# IntegratedSensor.net
KiCad netlist of a schematic drawn in EAGLE
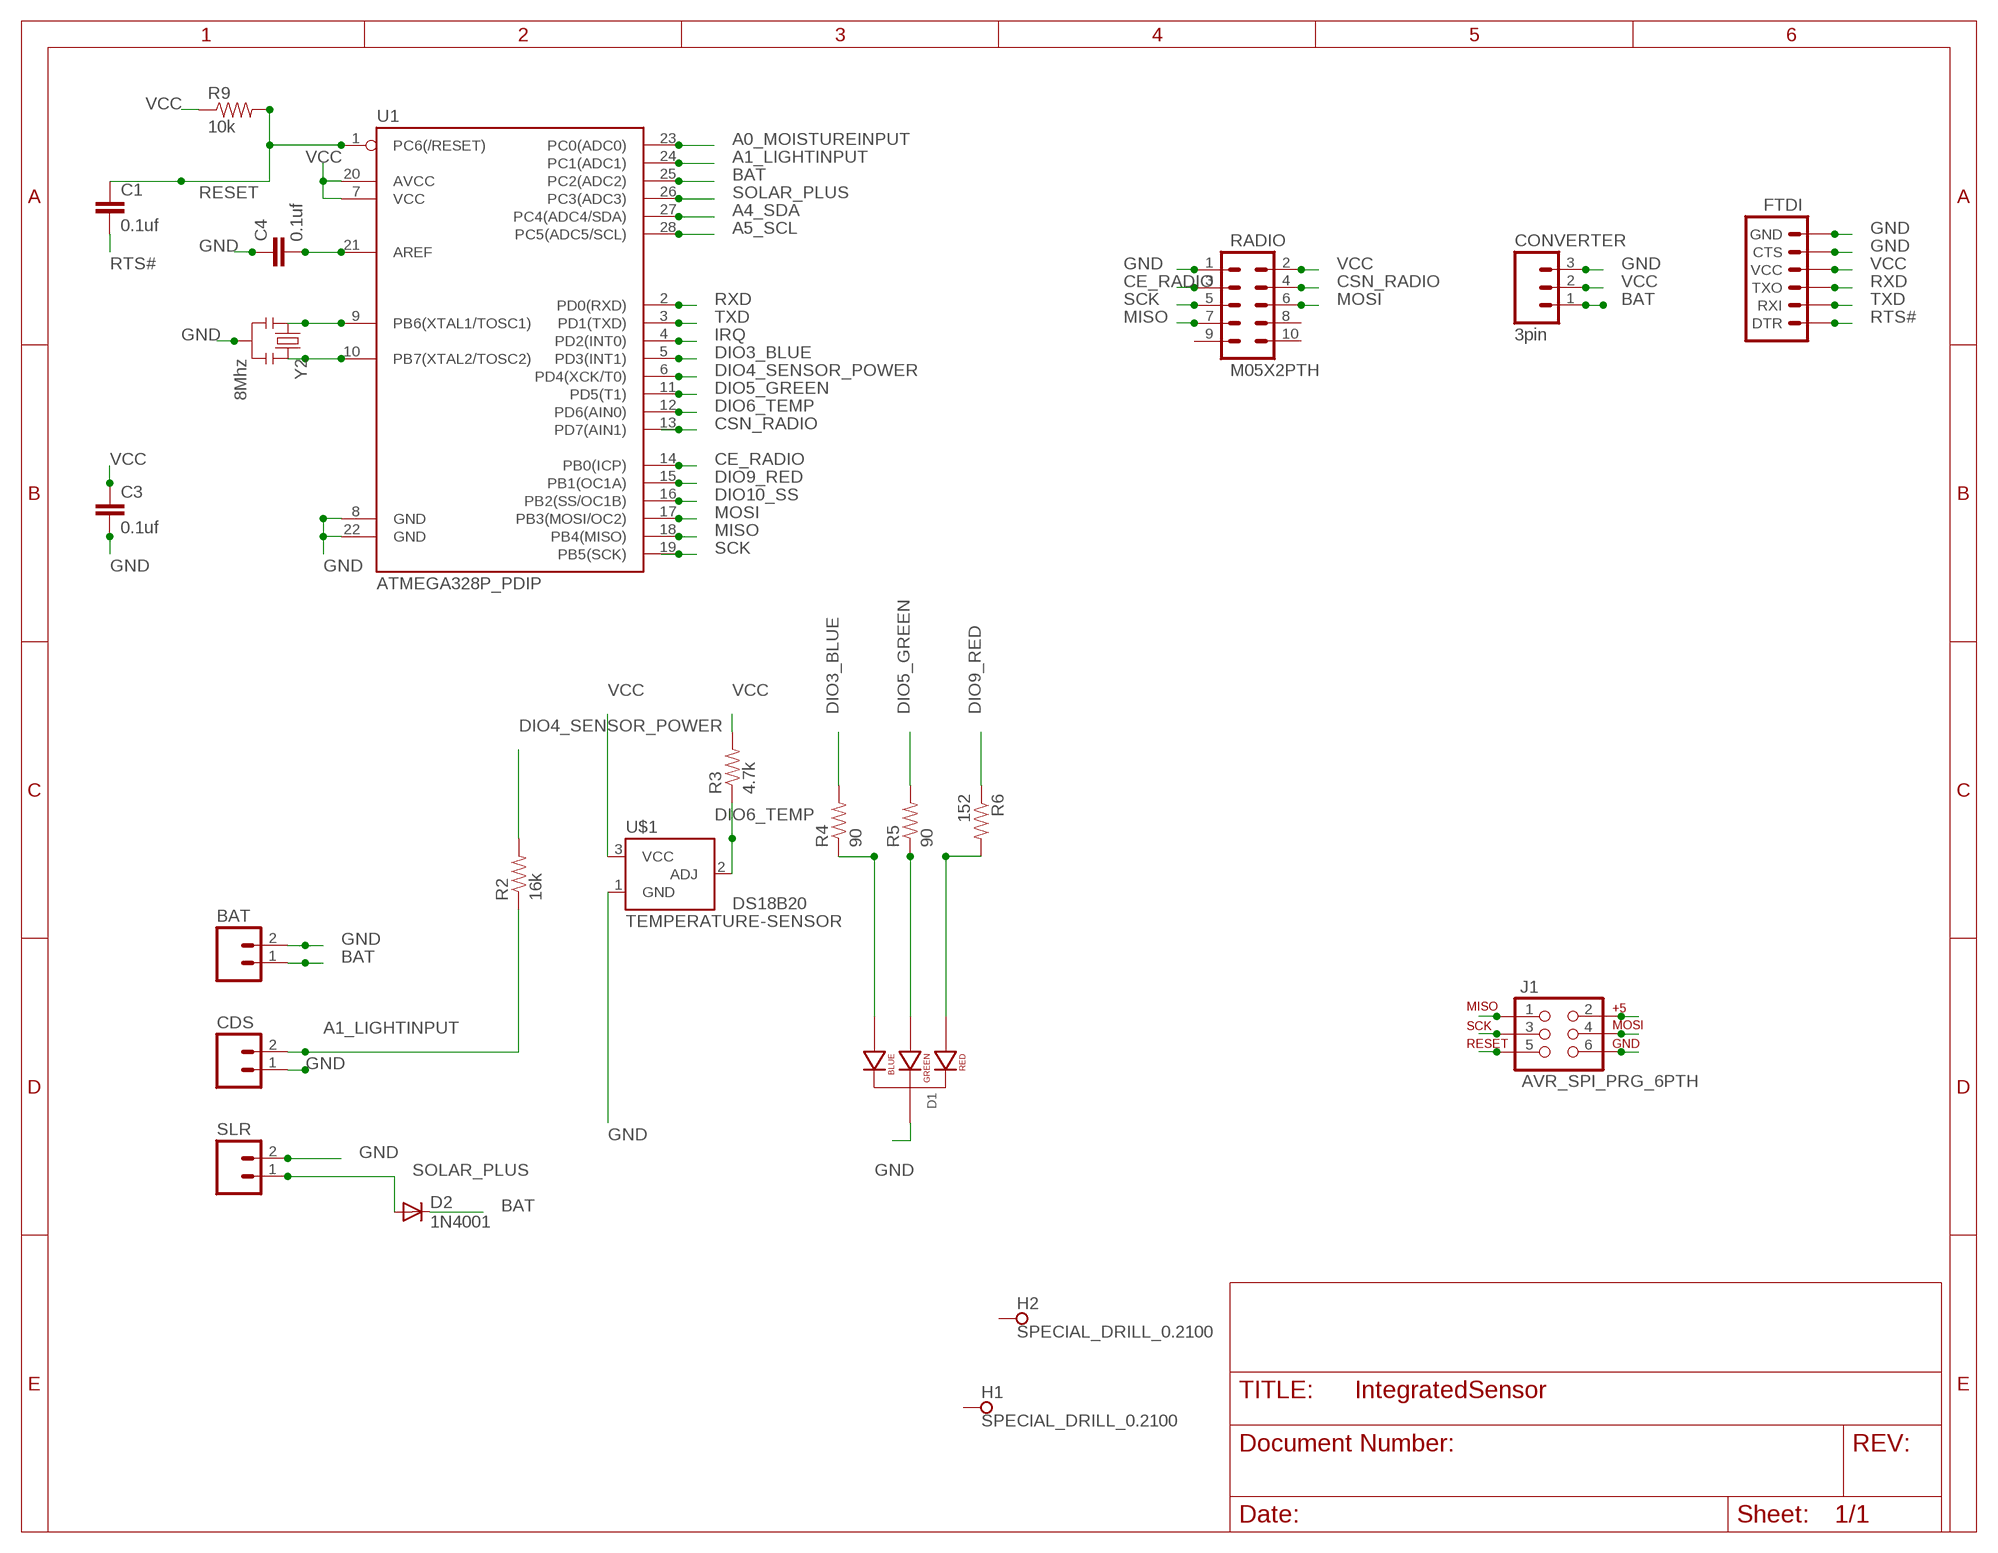
[diagram p0: schematic, sheet 1]

(export (version "E")
  (design (tool "Eeschema 10.0.6"))
  (components
    (comp (ref "BAT")
      (value "M02PTH")
      (footprint "eagle-import:1X02")
      (libsource (lib "eagle-import") (part "M02PTH"))
    )
    (comp (ref "C1")
      (value "0.1uf")
      (footprint "eagle-import:CAP-PTH-SMALL")
      (libsource (lib "eagle-import") (part "CAPPTH"))
    )
    (comp (ref "C3")
      (value "0.1uf")
      (footprint "eagle-import:CAP-PTH-SMALL")
      (libsource (lib "eagle-import") (part "CAPPTH"))
    )
    (comp (ref "C4")
      (value "0.1uf")
      (footprint "eagle-import:CAP-PTH-SMALL")
      (libsource (lib "eagle-import") (part "CAPPTH"))
    )
    (comp (ref "CDS")
      (value "M02PTH")
      (footprint "eagle-import:1X02")
      (libsource (lib "eagle-import") (part "M02PTH"))
    )
    (comp (ref "CONVERTER")
      (value "3pin")
      (footprint "eagle-import:1X03")
      (libsource (lib "eagle-import") (part "M03PTH"))
    )
    (comp (ref "D1")
      (value "LED-RGB-CC-THRUCLEAR")
      (footprint "eagle-import:LED-RGB-THRU")
      (libsource (lib "eagle-import") (part "LED-RGB-CC-THRUCLEAR"))
    )
    (comp (ref "D2")
      (value "1N4001")
      (footprint "eagle-import:DIODE-1N4001")
      (libsource (lib "eagle-import") (part "DIODEPTH"))
    )
    (comp (ref "FTDI")
      (value "ARDUINO_SERIAL_PROGRAMPTH")
      (footprint "eagle-import:1X06")
      (libsource (lib "eagle-import") (part "ARDUINO_SERIAL_PROGRAMPTH"))
    )
    (comp (ref "H1")
      (value "SPECIAL_DRILL_0.2100")
      (footprint "eagle-import:PAD_0.2100")
      (libsource (lib "eagle-import") (part "SPECIAL_DRILL_0.2100"))
    )
    (comp (ref "H2")
      (value "SPECIAL_DRILL_0.2100")
      (footprint "eagle-import:PAD_0.2100")
      (libsource (lib "eagle-import") (part "SPECIAL_DRILL_0.2100"))
    )
    (comp (ref "J1")
      (value "AVR_SPI_PRG_6PTH")
      (footprint "eagle-import:2X3")
      (libsource (lib "eagle-import") (part "AVR_SPI_PRG_6PTH"))
    )
    (comp (ref "R2")
      (value "16k")
      (footprint "eagle-import:1_6W-RES")
      (libsource (lib "eagle-import") (part "RESISTORPTH-1/6W"))
    )
    (comp (ref "R3")
      (value "4.7k")
      (footprint "eagle-import:1_6W-RES")
      (libsource (lib "eagle-import") (part "RESISTORPTH-1/6W"))
    )
    (comp (ref "R4")
      (value "90")
      (footprint "eagle-import:1_6W-RES")
      (libsource (lib "eagle-import") (part "RESISTORPTH-1/6W"))
    )
    (comp (ref "R5")
      (value "90")
      (footprint "eagle-import:1_6W-RES")
      (libsource (lib "eagle-import") (part "RESISTORPTH-1/6W"))
    )
    (comp (ref "R6")
      (value "152")
      (footprint "eagle-import:1_6W-RES")
      (libsource (lib "eagle-import") (part "RESISTORPTH-1/6W"))
    )
    (comp (ref "R9")
      (value "10k")
      (footprint "eagle-import:1_6W-RES")
      (libsource (lib "eagle-import") (part "RESISTORPTH-1/6W"))
    )
    (comp (ref "RADIO")
      (value "M05X2PTH")
      (footprint "eagle-import:AVR_ICSP")
      (libsource (lib "eagle-import") (part "M05X2PTH"))
    )
    (comp (ref "SLR")
      (value "M02PTH")
      (footprint "eagle-import:1X02")
      (libsource (lib "eagle-import") (part "M02PTH"))
    )
    (comp (ref "U$1")
      (value "TEMPERATURE-SENSOR")
      (footprint "eagle-import:TO-92")
      (fields (field (name "PARTNAME") "DS18B20"))
      (libsource (lib "eagle-import") (part "TEMPERATURE-SENSOR"))
    )
    (comp (ref "U1")
      (value "ATMEGA328P_PDIP")
      (footprint "eagle-import:DIL28-3")
      (libsource (lib "eagle-import") (part "ATMEGA328P_PDIP"))
    )
    (comp (ref "Y2")
      (value "8Mhz")
      (footprint "eagle-import:RESONATOR-PTH")
      (libsource (lib "eagle-import") (part "RESONATORPTH"))
    )
  )
  (nets
    (net (code "1") (name "/A0_MOISTUREINPUT") (class "Default")
      (node (ref "U1") (pin "23") (pinfunction "PC0(ADC0)_23") (pintype "bidirectional"))
    )
    (net (code "2") (name "/A1_LIGHTINPUT") (class "Default")
      (node (ref "CDS") (pin "2") (pinfunction "2_2") (pintype "passive"))
      (node (ref "R2") (pin "1") (pinfunction "1_1") (pintype "passive"))
      (node (ref "U1") (pin "24") (pinfunction "PC1(ADC1)_24") (pintype "bidirectional"))
    )
    (net (code "3") (name "/A4_SDA") (class "Default")
      (node (ref "U1") (pin "27") (pinfunction "PC4(ADC4/SDA)_27") (pintype "bidirectional"))
    )
    (net (code "4") (name "/A5_SCL") (class "Default")
      (node (ref "U1") (pin "28") (pinfunction "PC5(ADC5/SCL)_28") (pintype "bidirectional"))
    )
    (net (code "5") (name "/BAT") (class "Default")
      (node (ref "BAT") (pin "1") (pinfunction "1_1") (pintype "passive"))
      (node (ref "CONVERTER") (pin "1") (pinfunction "1_1") (pintype "passive"))
      (node (ref "D2") (pin "C") (pinfunction "C_C") (pintype "passive"))
      (node (ref "U1") (pin "25") (pinfunction "PC2(ADC2)_25") (pintype "bidirectional"))
    )
    (net (code "6") (name "/CE_RADIO") (class "Default")
      (node (ref "RADIO") (pin "3") (pinfunction "3_3") (pintype "passive"))
      (node (ref "U1") (pin "14") (pinfunction "PB0(ICP)_14") (pintype "bidirectional"))
    )
    (net (code "7") (name "/CSN_RADIO") (class "Default")
      (node (ref "RADIO") (pin "4") (pinfunction "4_4") (pintype "passive"))
      (node (ref "U1") (pin "13") (pinfunction "PD7(AIN1)_13") (pintype "bidirectional"))
    )
    (net (code "8") (name "/DIO3_BLUE") (class "Default")
      (node (ref "R4") (pin "2") (pinfunction "2_2") (pintype "passive"))
      (node (ref "U1") (pin "5") (pinfunction "PD3(INT1)_5") (pintype "bidirectional"))
    )
    (net (code "9") (name "/DIO4_SENSOR_POWER") (class "Default")
      (node (ref "R2") (pin "2") (pinfunction "2_2") (pintype "passive"))
      (node (ref "U1") (pin "6") (pinfunction "PD4(XCK/T0)_6") (pintype "bidirectional"))
    )
    (net (code "10") (name "/DIO5_GREEN") (class "Default")
      (node (ref "R5") (pin "2") (pinfunction "2_2") (pintype "passive"))
      (node (ref "U1") (pin "11") (pinfunction "PD5(T1)_11") (pintype "bidirectional"))
    )
    (net (code "11") (name "/DIO6_TEMP") (class "Default")
      (node (ref "R3") (pin "1") (pinfunction "1_1") (pintype "passive"))
      (node (ref "U$1") (pin "2") (pinfunction "ADJ_2") (pintype "bidirectional"))
      (node (ref "U1") (pin "12") (pinfunction "PD6(AIN0)_12") (pintype "bidirectional"))
    )
    (net (code "12") (name "/DIO9_RED") (class "Default")
      (node (ref "R6") (pin "1") (pinfunction "1_1") (pintype "passive"))
      (node (ref "U1") (pin "15") (pinfunction "PB1(OC1A)_15") (pintype "bidirectional"))
    )
    (net (code "13") (name "/DIO10_SS") (class "Default")
      (node (ref "U1") (pin "16") (pinfunction "PB2(SS/OC1B)_16") (pintype "bidirectional"))
    )
    (net (code "14") (name "/GND") (class "Default")
      (node (ref "BAT") (pin "2") (pinfunction "2_2") (pintype "passive"))
      (node (ref "C3") (pin "2") (pinfunction "2_2") (pintype "passive"))
      (node (ref "C4") (pin "1") (pinfunction "1_1") (pintype "passive"))
      (node (ref "CDS") (pin "1") (pinfunction "1_1") (pintype "passive"))
      (node (ref "CONVERTER") (pin "3") (pinfunction "3_3") (pintype "passive"))
      (node (ref "D1") (pin "2") (pinfunction "CATHODE_2") (pintype "bidirectional"))
      (node (ref "FTDI") (pin "5") (pinfunction "CTS_5") (pintype "passive"))
      (node (ref "FTDI") (pin "6") (pinfunction "GND_6") (pintype "passive"))
      (node (ref "J1") (pin "6") (pinfunction "6_6") (pintype "passive"))
      (node (ref "RADIO") (pin "1") (pinfunction "1_1") (pintype "passive"))
      (node (ref "SLR") (pin "2") (pinfunction "2_2") (pintype "passive"))
      (node (ref "U$1") (pin "1") (pinfunction "GND_1") (pintype "bidirectional"))
      (node (ref "U1") (pin "22") (pinfunction "GND_22") (pintype "bidirectional"))
      (node (ref "U1") (pin "8") (pinfunction "GND_8") (pintype "bidirectional"))
      (node (ref "Y2") (pin "2") (pinfunction "2_2") (pintype "passive"))
    )
    (net (code "15") (name "/IRQ") (class "Default")
      (node (ref "U1") (pin "4") (pinfunction "PD2(INT0)_4") (pintype "bidirectional"))
    )
    (net (code "16") (name "/MISO") (class "Default")
      (node (ref "J1") (pin "1") (pinfunction "1_1") (pintype "passive"))
      (node (ref "RADIO") (pin "7") (pinfunction "7_7") (pintype "passive"))
      (node (ref "U1") (pin "18") (pinfunction "PB4(MISO)_18") (pintype "bidirectional"))
    )
    (net (code "17") (name "/MOSI") (class "Default")
      (node (ref "J1") (pin "4") (pinfunction "4_4") (pintype "passive"))
      (node (ref "RADIO") (pin "6") (pinfunction "6_6") (pintype "passive"))
      (node (ref "U1") (pin "17") (pinfunction "PB3(MOSI/OC2)_17") (pintype "bidirectional"))
    )
    (net (code "18") (name "/RESET") (class "Default")
      (node (ref "C1") (pin "1") (pinfunction "1_1") (pintype "passive"))
      (node (ref "J1") (pin "5") (pinfunction "5_5") (pintype "passive"))
      (node (ref "R9") (pin "2") (pinfunction "2_2") (pintype "passive"))
      (node (ref "U1") (pin "1") (pinfunction "PC6(/RESET)_1") (pintype "bidirectional"))
    )
    (net (code "19") (name "/RTS#") (class "Default")
      (node (ref "C1") (pin "2") (pinfunction "2_2") (pintype "passive"))
      (node (ref "FTDI") (pin "1") (pinfunction "DTR_1") (pintype "passive"))
    )
    (net (code "20") (name "/RXD") (class "Default")
      (node (ref "FTDI") (pin "3") (pinfunction "TXO_3") (pintype "passive"))
      (node (ref "U1") (pin "2") (pinfunction "PD0(RXD)_2") (pintype "bidirectional"))
    )
    (net (code "21") (name "/SCK") (class "Default")
      (node (ref "J1") (pin "3") (pinfunction "3_3") (pintype "passive"))
      (node (ref "RADIO") (pin "5") (pinfunction "5_5") (pintype "passive"))
      (node (ref "U1") (pin "19") (pinfunction "PB5(SCK)_19") (pintype "bidirectional"))
    )
    (net (code "22") (name "/SOLAR_PLUS") (class "Default")
      (node (ref "D2") (pin "A") (pinfunction "A_A") (pintype "passive"))
      (node (ref "SLR") (pin "1") (pinfunction "1_1") (pintype "passive"))
      (node (ref "U1") (pin "26") (pinfunction "PC3(ADC3)_26") (pintype "bidirectional"))
    )
    (net (code "23") (name "/TXD") (class "Default")
      (node (ref "FTDI") (pin "2") (pinfunction "RXI_2") (pintype "passive"))
      (node (ref "U1") (pin "3") (pinfunction "PD1(TXD)_3") (pintype "bidirectional"))
    )
    (net (code "24") (name "/VCC") (class "Default")
      (node (ref "C3") (pin "1") (pinfunction "1_1") (pintype "passive"))
      (node (ref "CONVERTER") (pin "2") (pinfunction "2_2") (pintype "passive"))
      (node (ref "FTDI") (pin "4") (pinfunction "VCC_4") (pintype "passive"))
      (node (ref "J1") (pin "2") (pinfunction "2_2") (pintype "passive"))
      (node (ref "R3") (pin "2") (pinfunction "2_2") (pintype "passive"))
      (node (ref "R9") (pin "1") (pinfunction "1_1") (pintype "passive"))
      (node (ref "RADIO") (pin "2") (pinfunction "2_2") (pintype "passive"))
      (node (ref "U$1") (pin "3") (pinfunction "VCC_3") (pintype "bidirectional"))
      (node (ref "U1") (pin "20") (pinfunction "AVCC_20") (pintype "bidirectional"))
      (node (ref "U1") (pin "7") (pinfunction "VCC_7") (pintype "bidirectional"))
    )
    (net (code "25") (name "Net-(D1-BLUE_CATHODE)") (class "Default")
      (node (ref "D1") (pin "4") (pinfunction "BLUE_CATHODE_4") (pintype "bidirectional"))
      (node (ref "R4") (pin "1") (pinfunction "1_1") (pintype "passive"))
    )
    (net (code "26") (name "Net-(D1-GREEN_CATHODE)") (class "Default")
      (node (ref "D1") (pin "3") (pinfunction "GREEN_CATHODE_3") (pintype "bidirectional"))
      (node (ref "R5") (pin "1") (pinfunction "1_1") (pintype "passive"))
    )
    (net (code "27") (name "Net-(D1-RED_CATHODE)") (class "Default")
      (node (ref "D1") (pin "1") (pinfunction "RED_CATHODE_1") (pintype "bidirectional"))
      (node (ref "R6") (pin "2") (pinfunction "2_2") (pintype "passive"))
    )
    (net (code "28") (name "Net-(U1-AREF)") (class "Default")
      (node (ref "C4") (pin "2") (pinfunction "2_2") (pintype "passive"))
      (node (ref "U1") (pin "21") (pinfunction "AREF_21") (pintype "bidirectional"))
    )
    (net (code "29") (name "Net-(U1-PB6(XTAL1{slash}TOSC1))") (class "Default")
      (node (ref "U1") (pin "9") (pinfunction "PB6(XTAL1/TOSC1)_9") (pintype "bidirectional"))
      (node (ref "Y2") (pin "1") (pinfunction "1_1") (pintype "passive"))
    )
    (net (code "30") (name "Net-(U1-PB7(XTAL2{slash}TOSC2))") (class "Default")
      (node (ref "U1") (pin "10") (pinfunction "PB7(XTAL2/TOSC2)_10") (pintype "bidirectional"))
      (node (ref "Y2") (pin "3") (pinfunction "3_3") (pintype "passive"))
    )
    (net (code "31") (name "unconnected-(H1-Pad1)") (class "Default")
      (node (ref "H1") (pin "1") (pinfunction "1_1") (pintype "passive"))
    )
    (net (code "32") (name "unconnected-(H2-Pad1)") (class "Default")
      (node (ref "H2") (pin "1") (pinfunction "1_1") (pintype "passive"))
    )
    (net (code "33") (name "unconnected-(RADIO-Pad8)") (class "Default")
      (node (ref "RADIO") (pin "8") (pinfunction "8_8") (pintype "passive"))
    )
    (net (code "34") (name "unconnected-(RADIO-Pad9)") (class "Default")
      (node (ref "RADIO") (pin "9") (pinfunction "9_9") (pintype "passive"))
    )
    (net (code "35") (name "unconnected-(RADIO-Pad10)") (class "Default")
      (node (ref "RADIO") (pin "10") (pinfunction "10_10") (pintype "passive"))
    )
  )
)
